# hbridge.net
KiCad netlist of a schematic drawn in EAGLE
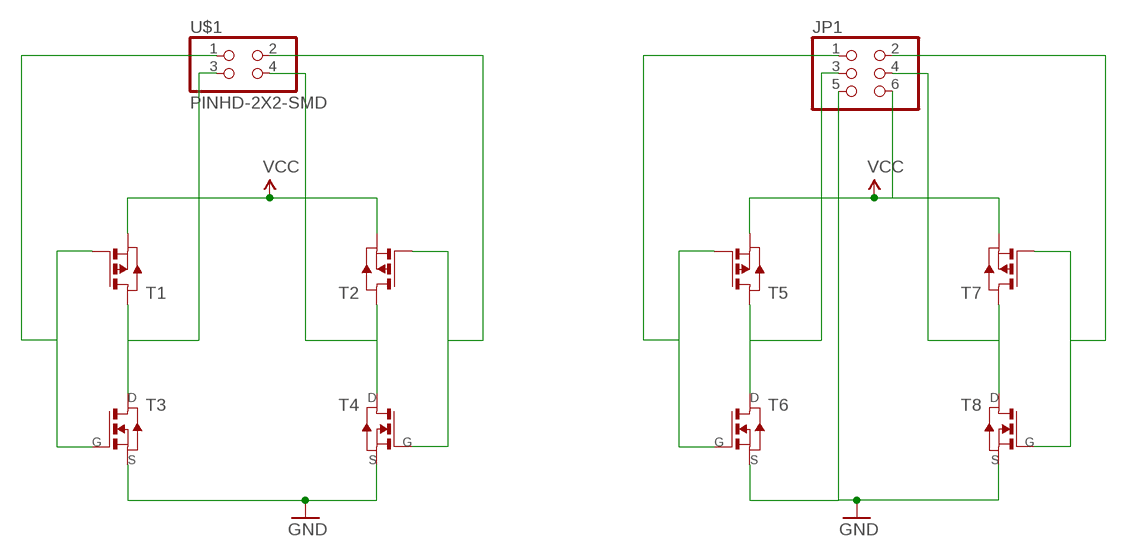
[diagram p0: schematic, sheet 1]

(export (version "E")
  (design (tool "Eeschema 10.0.6"))
  (components
    (comp (ref "JP1")
      (value "PINHD-2X3-SMD")
      (footprint "eagle-import:2X03SMD")
      (libsource (lib "eagle-import") (part "PINHD-2X3-SMD"))
    )
    (comp (ref "T1")
      (value "PMOSFETSOT23")
      (footprint "eagle-import:SOT-23")
      (libsource (lib "eagle-import") (part "PMOSFETSOT23"))
    )
    (comp (ref "T2")
      (value "PMOSFETSOT23")
      (footprint "eagle-import:SOT-23")
      (libsource (lib "eagle-import") (part "PMOSFETSOT23"))
    )
    (comp (ref "T3")
      (value "NMOSFETSOT23")
      (footprint "eagle-import:SOT-23")
      (libsource (lib "eagle-import") (part "NMOSFETSOT23"))
    )
    (comp (ref "T4")
      (value "NMOSFETSOT23")
      (footprint "eagle-import:SOT-23")
      (libsource (lib "eagle-import") (part "NMOSFETSOT23"))
    )
    (comp (ref "T5")
      (value "PMOSFETSOT23")
      (footprint "eagle-import:SOT-23")
      (libsource (lib "eagle-import") (part "PMOSFETSOT23"))
    )
    (comp (ref "T6")
      (value "NMOSFETSOT23")
      (footprint "eagle-import:SOT-23")
      (libsource (lib "eagle-import") (part "NMOSFETSOT23"))
    )
    (comp (ref "T7")
      (value "PMOSFETSOT23")
      (footprint "eagle-import:SOT-23")
      (libsource (lib "eagle-import") (part "PMOSFETSOT23"))
    )
    (comp (ref "T8")
      (value "NMOSFETSOT23")
      (footprint "eagle-import:SOT-23")
      (libsource (lib "eagle-import") (part "NMOSFETSOT23"))
    )
    (comp (ref "U$1")
      (value "PINHD-2X2-SMD")
      (footprint "eagle-import:2X02SMD")
      (libsource (lib "eagle-import") (part "PINHD-2X2-SMD"))
    )
  )
  (nets
    (net (code "1") (name "GND") (class "Default")
      (node (ref "JP1") (pin "5") (pinfunction "5_5") (pintype "passive"))
      (node (ref "T3") (pin "2") (pinfunction "S_2") (pintype "passive"))
      (node (ref "T4") (pin "2") (pinfunction "S_2") (pintype "passive"))
      (node (ref "T6") (pin "2") (pinfunction "S_2") (pintype "passive"))
      (node (ref "T8") (pin "2") (pinfunction "S_2") (pintype "passive"))
    )
    (net (code "2") (name "Net-(T1-D)") (class "Default")
      (node (ref "T1") (pin "1") (pinfunction "D_1") (pintype "passive"))
      (node (ref "T3") (pin "1") (pinfunction "D_1") (pintype "passive"))
      (node (ref "U$1") (pin "3") (pinfunction "3_3") (pintype "passive"))
    )
    (net (code "3") (name "Net-(T1-G)") (class "Default")
      (node (ref "T1") (pin "3") (pinfunction "G_3") (pintype "passive"))
      (node (ref "T3") (pin "3") (pinfunction "G_3") (pintype "passive"))
      (node (ref "U$1") (pin "1") (pinfunction "1_1") (pintype "passive"))
    )
    (net (code "4") (name "Net-(T2-D)") (class "Default")
      (node (ref "T2") (pin "1") (pinfunction "D_1") (pintype "passive"))
      (node (ref "T4") (pin "1") (pinfunction "D_1") (pintype "passive"))
      (node (ref "U$1") (pin "4") (pinfunction "4_4") (pintype "passive"))
    )
    (net (code "5") (name "Net-(T2-G)") (class "Default")
      (node (ref "T2") (pin "3") (pinfunction "G_3") (pintype "passive"))
      (node (ref "T4") (pin "3") (pinfunction "G_3") (pintype "passive"))
      (node (ref "U$1") (pin "2") (pinfunction "2_2") (pintype "passive"))
    )
    (net (code "6") (name "Net-(T5-D)") (class "Default")
      (node (ref "JP1") (pin "3") (pinfunction "3_3") (pintype "passive"))
      (node (ref "T5") (pin "1") (pinfunction "D_1") (pintype "passive"))
      (node (ref "T6") (pin "1") (pinfunction "D_1") (pintype "passive"))
    )
    (net (code "7") (name "Net-(T5-G)") (class "Default")
      (node (ref "JP1") (pin "1") (pinfunction "1_1") (pintype "passive"))
      (node (ref "T5") (pin "3") (pinfunction "G_3") (pintype "passive"))
      (node (ref "T6") (pin "3") (pinfunction "G_3") (pintype "passive"))
    )
    (net (code "8") (name "Net-(T7-D)") (class "Default")
      (node (ref "JP1") (pin "4") (pinfunction "4_4") (pintype "passive"))
      (node (ref "T7") (pin "1") (pinfunction "D_1") (pintype "passive"))
      (node (ref "T8") (pin "1") (pinfunction "D_1") (pintype "passive"))
    )
    (net (code "9") (name "Net-(T7-G)") (class "Default")
      (node (ref "JP1") (pin "2") (pinfunction "2_2") (pintype "passive"))
      (node (ref "T7") (pin "3") (pinfunction "G_3") (pintype "passive"))
      (node (ref "T8") (pin "3") (pinfunction "G_3") (pintype "passive"))
    )
    (net (code "10") (name "VCC") (class "Default")
      (node (ref "JP1") (pin "6") (pinfunction "6_6") (pintype "passive"))
      (node (ref "T1") (pin "2") (pinfunction "S_2") (pintype "passive"))
      (node (ref "T2") (pin "2") (pinfunction "S_2") (pintype "passive"))
      (node (ref "T5") (pin "2") (pinfunction "S_2") (pintype "passive"))
      (node (ref "T7") (pin "2") (pinfunction "S_2") (pintype "passive"))
    )
  )
)
